# 02_Power_Supply.net
KiCad netlist of a schematic drawn in Altium Designer
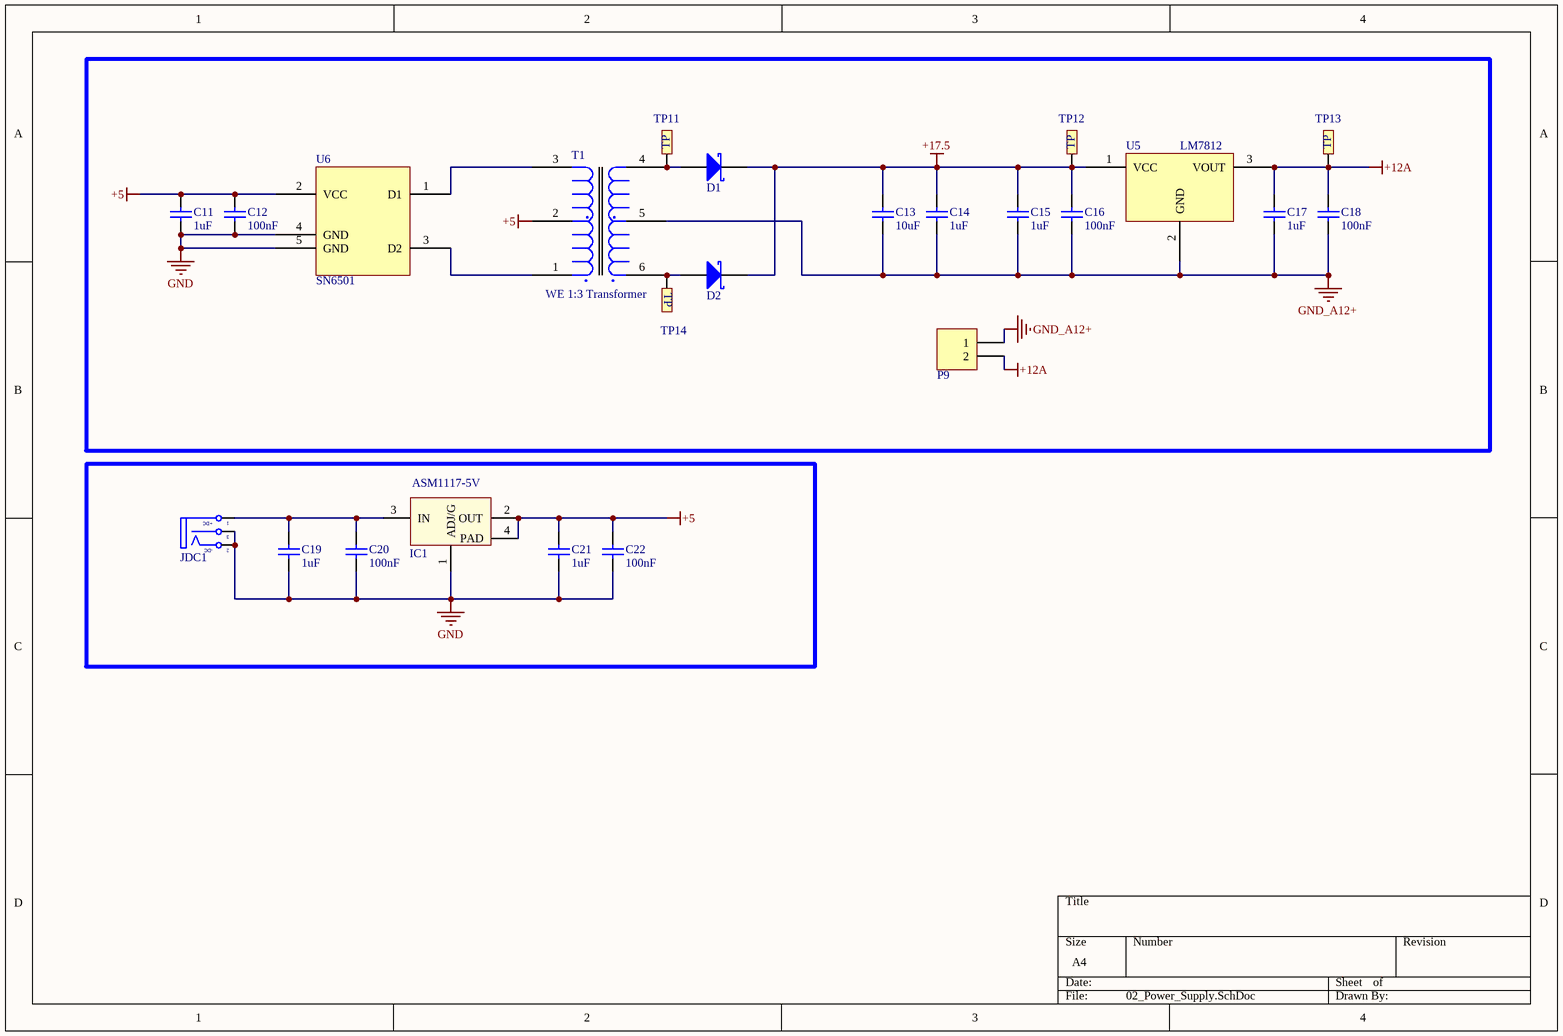
[diagram p0: 02_Power_Supply.SchDoc]

(export (version "E")
  (design (tool "Eeschema 10.0.6"))
  (components
    (comp (ref "C11")
      (value "1uF")
      (footprint "CAP-SM-0805")
      (description "Capacitor")
      (fields (field (name "Comment") "Cap Non-Pol SMD"))
      (libsource (lib "PIF_Library") (part "Cap Non-Pol SMD"))
    )
    (comp (ref "C12")
      (value "100nF")
      (footprint "CAP-SM-0805")
      (description "Capacitor")
      (fields (field (name "Comment") "Cap Non-Pol SMD"))
      (libsource (lib "PIF_Library") (part "Cap Non-Pol SMD"))
    )
    (comp (ref "C13")
      (value "10uF")
      (footprint "CAP-SM-0805")
      (description "Capacitor")
      (fields (field (name "Comment") "Cap Non-Pol SMD"))
      (libsource (lib "PIF_Library") (part "Cap Non-Pol SMD"))
    )
    (comp (ref "C14")
      (value "1uF")
      (footprint "CAP-SM-0805")
      (description "Capacitor")
      (fields (field (name "Comment") "Cap Non-Pol SMD"))
      (libsource (lib "PIF_Library") (part "Cap Non-Pol SMD"))
    )
    (comp (ref "C15")
      (value "1uF")
      (footprint "CAP-SM-0805")
      (description "Capacitor")
      (fields (field (name "Comment") "Cap Non-Pol SMD"))
      (libsource (lib "PIF_Library") (part "Cap Non-Pol SMD"))
    )
    (comp (ref "C16")
      (value "100nF")
      (footprint "CAP-SM-0805")
      (description "Capacitor")
      (fields (field (name "Comment") "Cap Non-Pol SMD"))
      (libsource (lib "PIF_Library") (part "Cap Non-Pol SMD"))
    )
    (comp (ref "C17")
      (value "1uF")
      (footprint "CAP-SM-0805")
      (description "Capacitor")
      (fields (field (name "Comment") "Cap Non-Pol SMD"))
      (libsource (lib "PIF_Library") (part "Cap Non-Pol SMD"))
    )
    (comp (ref "C18")
      (value "100nF")
      (footprint "CAP-SM-0805")
      (description "Capacitor")
      (fields (field (name "Comment") "Cap Non-Pol SMD"))
      (libsource (lib "PIF_Library") (part "Cap Non-Pol SMD"))
    )
    (comp (ref "C19")
      (value "1uF")
      (footprint "CAP-SM-0805")
      (description "Capacitor")
      (fields (field (name "Comment") "Cap Non-Pol SMD"))
      (libsource (lib "PIF_Library") (part "Cap Non-Pol SMD"))
    )
    (comp (ref "C20")
      (value "100nF")
      (footprint "CAP-SM-0805")
      (description "Capacitor")
      (fields (field (name "Comment") "Cap Non-Pol SMD"))
      (libsource (lib "PIF_Library") (part "Cap Non-Pol SMD"))
    )
    (comp (ref "C21")
      (value "1uF")
      (footprint "CAP-SM-0805")
      (description "Capacitor")
      (fields (field (name "Comment") "Cap Non-Pol SMD"))
      (libsource (lib "PIF_Library") (part "Cap Non-Pol SMD"))
    )
    (comp (ref "C22")
      (value "100nF")
      (footprint "CAP-SM-0805")
      (description "Capacitor")
      (fields (field (name "Comment") "Cap Non-Pol SMD"))
      (libsource (lib "PIF_Library") (part "Cap Non-Pol SMD"))
    )
    (comp (ref "D1")
      (value "D Schottky")
      (footprint "SS34")
      (description "Schottky Diode")
      (fields (field (name "PUBLISHER") "Altium Limited"))
      (libsource (lib "PIF_Library") (part "D Schottky"))
    )
    (comp (ref "D2")
      (value "D Schottky")
      (footprint "SS34")
      (description "Schottky Diode")
      (fields (field (name "PUBLISHER") "Altium Limited"))
      (libsource (lib "PIF_Library") (part "D Schottky"))
    )
    (comp (ref "IC1")
      (value "ASM1117-5V")
      (footprint "SOT223-4N")
      (description "Available in 1.8V, 2.5V, 2.85V, 3.3V, 5V, and  Adjustable Versions")
      (libsource (lib "PIF_Library") (part "LM1117"))
    )
    (comp (ref "JDC1")
      (value "Jack DC")
      (footprint "DC-IN")
      (description "Jack DC input")
      (libsource (lib "PIF_Library") (part "Jack DC"))
    )
    (comp (ref "P9")
      (value "Domino 2")
      (footprint "DOMINO 2- 5mm")
      (description "Domino, 2-Pin")
      (fields (field (name "PUBLISHER") "Altium Limited"))
      (libsource (lib "PIF_Library") (part "Domino 2"))
    )
    (comp (ref "T1")
      (value "WE 1:3 Transformer")
      (footprint "750316818")
      (fields (field (name "MANUFACTURER") "Wurth Elektronik"))
      (libsource (lib "MiclsLib") (part "WE 1{colon}3.5 Transformer"))
    )
    (comp (ref "TP11")
      (value "Test Point")
      (footprint "TP")
      (libsource (lib "PIF_Library") (part "Test Point"))
    )
    (comp (ref "TP12")
      (value "Test Point")
      (footprint "TP")
      (libsource (lib "PIF_Library") (part "Test Point"))
    )
    (comp (ref "TP13")
      (value "Test Point")
      (footprint "TP")
      (libsource (lib "PIF_Library") (part "Test Point"))
    )
    (comp (ref "TP14") (value "Test Point") (footprint "TP") (libsource (lib "") (part "Test Point_1")))
    (comp (ref "U5")
      (value "LM7812")
      (footprint "DPAK228P1014X239-3N")
      (libsource (lib "MiclsLib") (part "LM78xx"))
    )
    (comp (ref "U6")
      (value "SN6501")
      (footprint "SOT95P280X145-5N")
      (libsource (lib "MiclsLib") (part "SN6501"))
    )
  )
  (nets
    (net (code "1") (name "+5") (class "Default")
      (node (ref "C11") (pin "2") (pinfunction "2_2") (pintype "passive"))
      (node (ref "C12") (pin "2") (pinfunction "2_2") (pintype "passive"))
      (node (ref "C21") (pin "2") (pinfunction "2_2") (pintype "passive"))
      (node (ref "C22") (pin "2") (pinfunction "2_2") (pintype "passive"))
      (node (ref "IC1") (pin "2") (pinfunction "OUT_2") (pintype "passive"))
      (node (ref "IC1") (pin "4") (pinfunction "PAD_4") (pintype "passive"))
      (node (ref "T1") (pin "2") (pinfunction "2_2") (pintype "passive"))
      (node (ref "U6") (pin "2") (pinfunction "VCC_2") (pintype "passive"))
    )
    (net (code "2") (name "+12A") (class "Default")
      (node (ref "C17") (pin "2") (pinfunction "2_2") (pintype "passive"))
      (node (ref "C18") (pin "2") (pinfunction "2_2") (pintype "passive"))
      (node (ref "P9") (pin "2") (pinfunction "2_2") (pintype "passive"))
      (node (ref "TP13") (pin "TP1") (pinfunction "0_TP1") (pintype "passive"))
      (node (ref "U5") (pin "3") (pinfunction "VOUT_3") (pintype "passive"))
    )
    (net (code "3") (name "+17.5") (class "Default")
      (node (ref "C13") (pin "2") (pinfunction "2_2") (pintype "passive"))
      (node (ref "C14") (pin "2") (pinfunction "2_2") (pintype "passive"))
      (node (ref "C15") (pin "2") (pinfunction "2_2") (pintype "passive"))
      (node (ref "C16") (pin "2") (pinfunction "2_2") (pintype "passive"))
      (node (ref "D1") (pin "2") (pinfunction "K_2") (pintype "passive"))
      (node (ref "D2") (pin "2") (pinfunction "K_2") (pintype "passive"))
      (node (ref "TP12") (pin "TP1") (pinfunction "0_TP1") (pintype "passive"))
      (node (ref "U5") (pin "1") (pinfunction "VCC_1") (pintype "passive"))
    )
    (net (code "4") (name "GND") (class "Default")
      (node (ref "C11") (pin "1") (pinfunction "1_1") (pintype "passive"))
      (node (ref "C12") (pin "1") (pinfunction "1_1") (pintype "passive"))
      (node (ref "C19") (pin "1") (pinfunction "1_1") (pintype "passive"))
      (node (ref "C20") (pin "1") (pinfunction "1_1") (pintype "passive"))
      (node (ref "C21") (pin "1") (pinfunction "1_1") (pintype "passive"))
      (node (ref "C22") (pin "1") (pinfunction "1_1") (pintype "passive"))
      (node (ref "IC1") (pin "1") (pinfunction "ADJ/G_1") (pintype "passive"))
      (node (ref "JDC1") (pin "2") (pinfunction "TN_2") (pintype "passive"))
      (node (ref "JDC1") (pin "3") (pinfunction "S_3") (pintype "power_in"))
      (node (ref "U6") (pin "4") (pinfunction "GND_4") (pintype "passive"))
      (node (ref "U6") (pin "5") (pinfunction "GND_5") (pintype "passive"))
    )
    (net (code "5") (name "GND_A12+") (class "Default")
      (node (ref "C13") (pin "1") (pinfunction "1_1") (pintype "passive"))
      (node (ref "C14") (pin "1") (pinfunction "1_1") (pintype "passive"))
      (node (ref "C15") (pin "1") (pinfunction "1_1") (pintype "passive"))
      (node (ref "C16") (pin "1") (pinfunction "1_1") (pintype "passive"))
      (node (ref "C17") (pin "1") (pinfunction "1_1") (pintype "passive"))
      (node (ref "C18") (pin "1") (pinfunction "1_1") (pintype "passive"))
      (node (ref "P9") (pin "1") (pinfunction "1_1") (pintype "passive"))
      (node (ref "T1") (pin "5") (pinfunction "5_5") (pintype "passive"))
      (node (ref "U5") (pin "2") (pinfunction "GND_2") (pintype "passive"))
    )
    (net (code "6") (name "Net-(D1-A)") (class "Default")
      (node (ref "D1") (pin "1") (pinfunction "A_1") (pintype "passive"))
      (node (ref "T1") (pin "4") (pinfunction "4_4") (pintype "passive"))
      (node (ref "TP11") (pin "TP1") (pinfunction "0_TP1") (pintype "passive"))
    )
    (net (code "7") (name "Net-(D2-A)") (class "Default")
      (node (ref "D2") (pin "1") (pinfunction "A_1") (pintype "passive"))
      (node (ref "T1") (pin "6") (pinfunction "6_6") (pintype "passive"))
      (node (ref "TP14") (pin "TP1") (pinfunction "0_TP1") (pintype "passive"))
    )
    (net (code "8") (name "Net-(IC1-IN)") (class "Default")
      (node (ref "C19") (pin "2") (pinfunction "2_2") (pintype "passive"))
      (node (ref "C20") (pin "2") (pinfunction "2_2") (pintype "passive"))
      (node (ref "IC1") (pin "3") (pinfunction "IN_3") (pintype "passive"))
      (node (ref "JDC1") (pin "1") (pinfunction "T_1") (pintype "passive"))
    )
    (net (code "9") (name "Net-(U6-D1)") (class "Default")
      (node (ref "T1") (pin "3") (pinfunction "3_3") (pintype "passive"))
      (node (ref "U6") (pin "1") (pinfunction "D1_1") (pintype "passive"))
    )
    (net (code "10") (name "Net-(U6-D2)") (class "Default")
      (node (ref "T1") (pin "1") (pinfunction "1_1") (pintype "passive"))
      (node (ref "U6") (pin "3") (pinfunction "D2_3") (pintype "passive"))
    )
  )
)
